# FTDI_breakout-v1_0.net
KiCad netlist of a schematic drawn in EAGLE
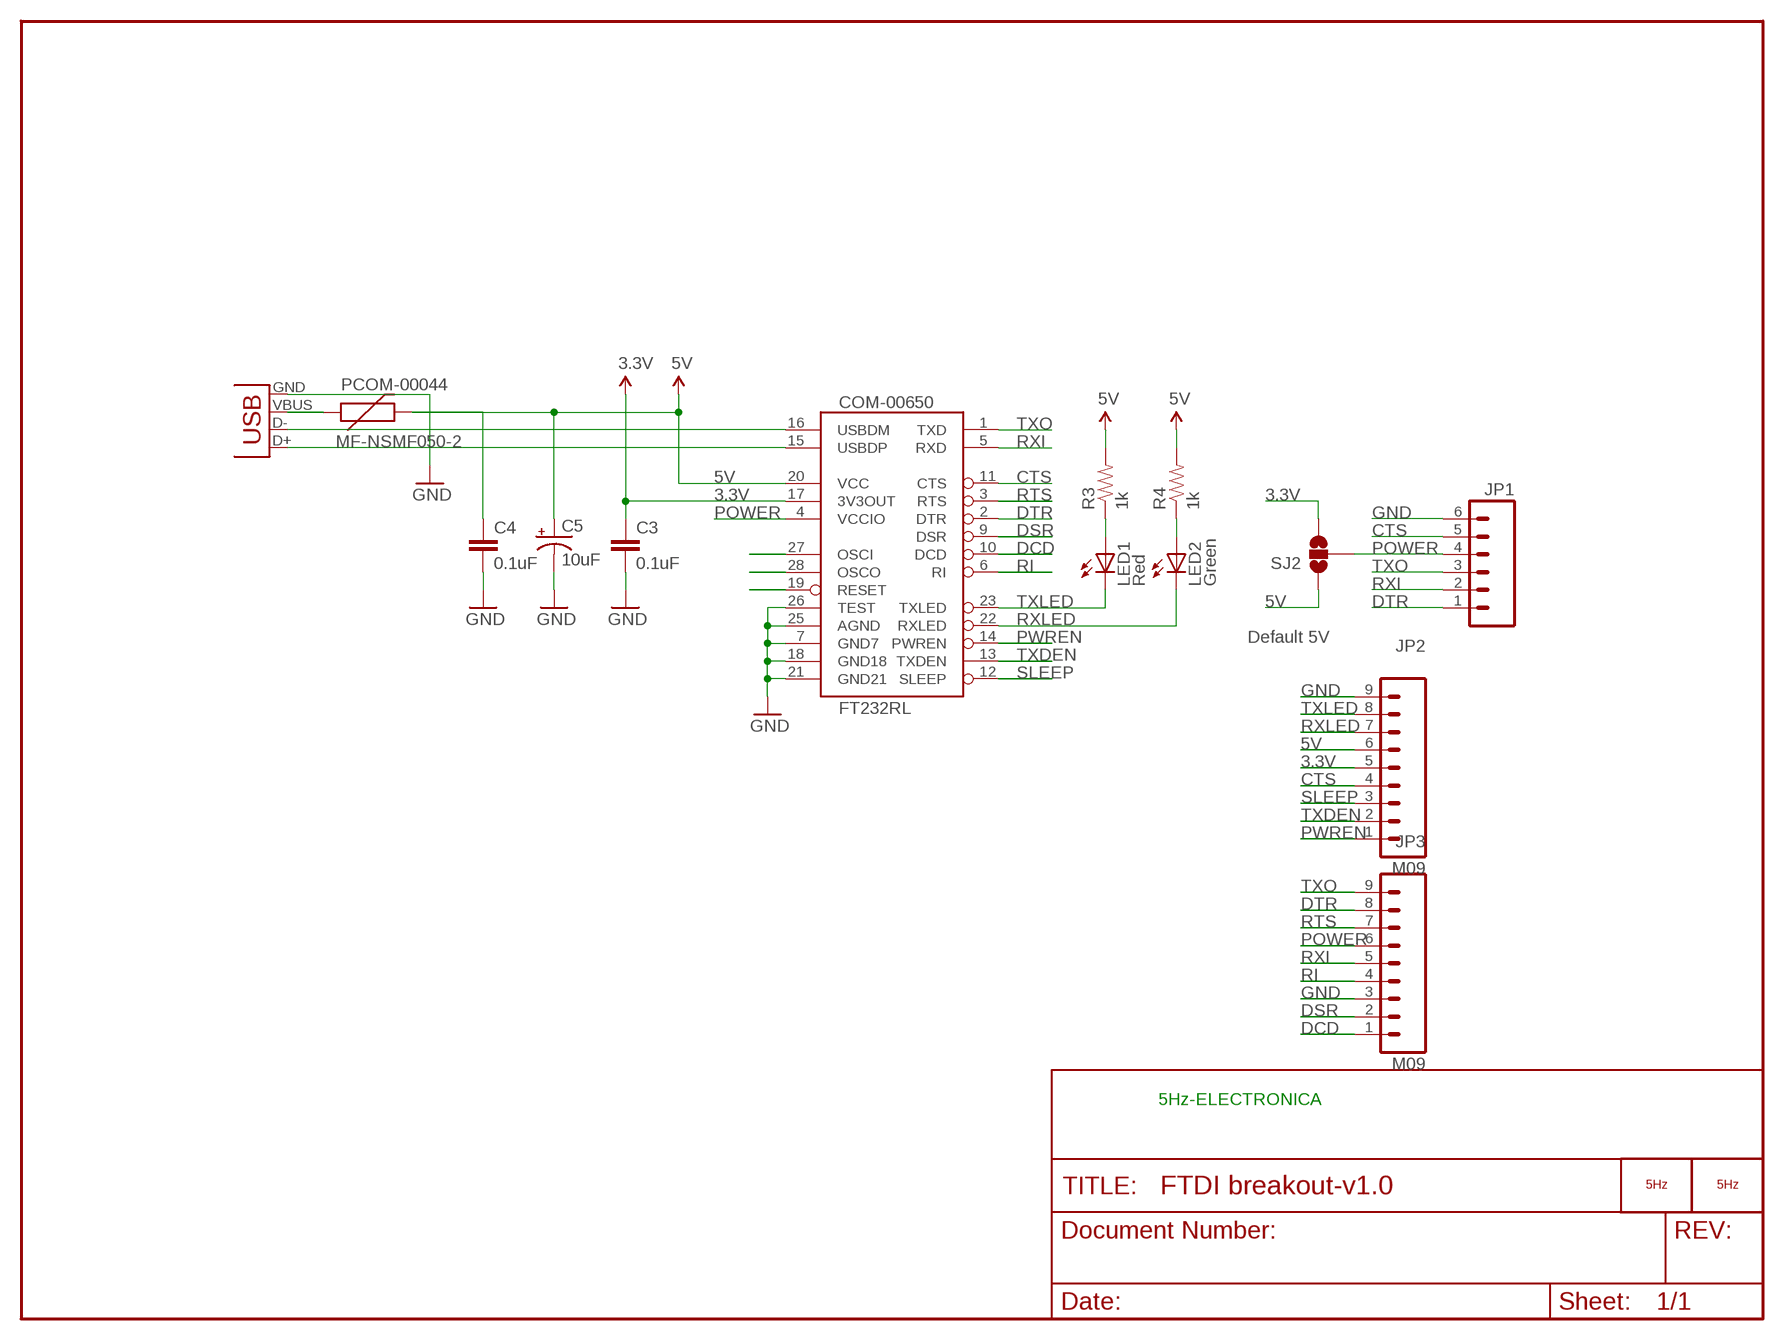
[diagram p0: schematic, sheet 1]

(export (version "E")
  (design (tool "Eeschema 10.0.6"))
  (components
    (comp (ref "C3")
      (value "0.1uF")
      (footprint "eagle-import:0603-CAP")
      (libsource (lib "eagle-import") (part "CAP0603-CAP"))
    )
    (comp (ref "C4")
      (value "0.1uF")
      (footprint "eagle-import:0603-CAP")
      (libsource (lib "eagle-import") (part "CAP0603-CAP"))
    )
    (comp (ref "C5")
      (value "10uF")
      (footprint "eagle-import:EIA3216")
      (libsource (lib "eagle-import") (part "CAP_POL1206"))
    )
    (comp (ref "COM-00650")
      (value "FT232RL")
      (footprint "eagle-import:SSOP28DB")
      (libsource (lib "eagle-import") (part "FT232RLSSOP"))
    )
    (comp (ref "JP1")
      (value "M06SIP")
      (footprint "eagle-import:1X06")
      (libsource (lib "eagle-import") (part "M06SIP"))
    )
    (comp (ref "JP2")
      (value "M09")
      (footprint "eagle-import:1X09")
      (libsource (lib "eagle-import") (part "M09"))
    )
    (comp (ref "JP3")
      (value "M09")
      (footprint "eagle-import:1X09")
      (libsource (lib "eagle-import") (part "M09"))
    )
    (comp (ref "LED1")
      (value "Red")
      (footprint "eagle-import:LED-0603")
      (libsource (lib "eagle-import") (part "LED0603"))
    )
    (comp (ref "LED2")
      (value "Green")
      (footprint "eagle-import:LED-0603")
      (libsource (lib "eagle-import") (part "LED0603"))
    )
    (comp (ref "LOGO1")
      (value "LOGO_5HZ_H_5MM")
      (footprint "eagle-import:5HZ_LOGO_H_5MM")
      (libsource (lib "eagle-import") (part "LOGO_5HZ_H_5MM"))
    )
    (comp (ref "LOGO2")
      (value "LOGO_5HZ_H_15MM")
      (footprint "eagle-import:5HZ_LOGO_H_15MM")
      (libsource (lib "eagle-import") (part "LOGO_5HZ_H_15MM"))
    )
    (comp (ref "PCOM-00044")
      (value "MF-NSMF050-2")
      (footprint "eagle-import:PTC-1206")
      (libsource (lib "eagle-import") (part "PTCSMD"))
    )
    (comp (ref "PRT-00587")
      (value "897-43-005-00-100001")
      (footprint "eagle-import:USB-MINIB")
      (libsource (lib "eagle-import") (part "USBSMD"))
    )
    (comp (ref "R3")
      (value "1k")
      (footprint "eagle-import:0603-RES")
      (libsource (lib "eagle-import") (part "RESISTOR0603-RES"))
    )
    (comp (ref "R4")
      (value "1k")
      (footprint "eagle-import:0603-RES")
      (libsource (lib "eagle-import") (part "RESISTOR0603-RES"))
    )
    (comp (ref "SJ2")
      (value "SOLDERJUMPER_2WAYS")
      (footprint "eagle-import:SJ_3")
      (libsource (lib "eagle-import") (part "SOLDERJUMPER_2WAYS"))
    )
  )
  (nets
    (net (code "1") (name "/CTS") (class "Default")
      (node (ref "COM-00650") (pin "11") (pinfunction "CTS_11") (pintype "input"))
      (node (ref "JP1") (pin "5") (pinfunction "5_5") (pintype "passive"))
      (node (ref "JP2") (pin "4") (pinfunction "4_4") (pintype "passive"))
    )
    (net (code "2") (name "/DCD") (class "Default")
      (node (ref "COM-00650") (pin "10") (pinfunction "DCD_10") (pintype "input"))
      (node (ref "JP3") (pin "1") (pinfunction "1_1") (pintype "passive"))
    )
    (net (code "3") (name "/DSR") (class "Default")
      (node (ref "COM-00650") (pin "9") (pinfunction "DSR_9") (pintype "input"))
      (node (ref "JP3") (pin "2") (pinfunction "2_2") (pintype "passive"))
    )
    (net (code "4") (name "/DTR") (class "Default")
      (node (ref "COM-00650") (pin "2") (pinfunction "DTR_2") (pintype "output"))
      (node (ref "JP1") (pin "1") (pinfunction "1_1") (pintype "passive"))
      (node (ref "JP3") (pin "8") (pinfunction "8_8") (pintype "passive"))
    )
    (net (code "5") (name "/POWER") (class "Default")
      (node (ref "COM-00650") (pin "4") (pinfunction "VCCIO_4") (pintype "power_in"))
      (node (ref "JP1") (pin "4") (pinfunction "4_4") (pintype "passive"))
      (node (ref "JP3") (pin "6") (pinfunction "6_6") (pintype "passive"))
      (node (ref "SJ2") (pin "2") (pinfunction "2_2") (pintype "passive"))
    )
    (net (code "6") (name "/PWREN") (class "Default")
      (node (ref "COM-00650") (pin "14") (pinfunction "PWREN_14") (pintype "input"))
      (node (ref "JP2") (pin "1") (pinfunction "1_1") (pintype "passive"))
    )
    (net (code "7") (name "/RI") (class "Default")
      (node (ref "COM-00650") (pin "6") (pinfunction "RI_6") (pintype "input"))
      (node (ref "JP3") (pin "4") (pinfunction "4_4") (pintype "passive"))
    )
    (net (code "8") (name "/RTS") (class "Default")
      (node (ref "COM-00650") (pin "3") (pinfunction "RTS_3") (pintype "output"))
      (node (ref "JP3") (pin "7") (pinfunction "7_7") (pintype "passive"))
    )
    (net (code "9") (name "/RXI") (class "Default")
      (node (ref "COM-00650") (pin "5") (pinfunction "RXD_5") (pintype "input"))
      (node (ref "JP1") (pin "2") (pinfunction "2_2") (pintype "passive"))
      (node (ref "JP3") (pin "5") (pinfunction "5_5") (pintype "passive"))
    )
    (net (code "10") (name "/RXLED") (class "Default")
      (node (ref "COM-00650") (pin "22") (pinfunction "RXLED_22") (pintype "input"))
      (node (ref "JP2") (pin "7") (pinfunction "7_7") (pintype "passive"))
      (node (ref "LED2") (pin "C") (pinfunction "C_C") (pintype "passive"))
    )
    (net (code "11") (name "/SLEEP") (class "Default")
      (node (ref "COM-00650") (pin "12") (pinfunction "SLEEP_12") (pintype "input"))
      (node (ref "JP2") (pin "3") (pinfunction "3_3") (pintype "passive"))
    )
    (net (code "12") (name "/TXDEN") (class "Default")
      (node (ref "COM-00650") (pin "13") (pinfunction "TXDEN_13") (pintype "input"))
      (node (ref "JP2") (pin "2") (pinfunction "2_2") (pintype "passive"))
    )
    (net (code "13") (name "/TXLED") (class "Default")
      (node (ref "COM-00650") (pin "23") (pinfunction "TXLED_23") (pintype "input"))
      (node (ref "JP2") (pin "8") (pinfunction "8_8") (pintype "passive"))
      (node (ref "LED1") (pin "C") (pinfunction "C_C") (pintype "passive"))
    )
    (net (code "14") (name "/TXO") (class "Default")
      (node (ref "COM-00650") (pin "1") (pinfunction "TXD_1") (pintype "output"))
      (node (ref "JP1") (pin "3") (pinfunction "3_3") (pintype "passive"))
      (node (ref "JP3") (pin "9") (pinfunction "9_9") (pintype "passive"))
    )
    (net (code "15") (name "3.3V") (class "Default")
      (node (ref "C3") (pin "1") (pinfunction "1_1") (pintype "passive"))
      (node (ref "COM-00650") (pin "17") (pinfunction "3V3OUT_17") (pintype "output"))
      (node (ref "JP2") (pin "5") (pinfunction "5_5") (pintype "passive"))
      (node (ref "SJ2") (pin "3") (pinfunction "3_3") (pintype "passive"))
    )
    (net (code "16") (name "5V") (class "Default")
      (node (ref "C4") (pin "1") (pinfunction "1_1") (pintype "passive"))
      (node (ref "C5") (pin "A") (pinfunction "+_A") (pintype "passive"))
      (node (ref "COM-00650") (pin "20") (pinfunction "VCC_20") (pintype "power_in"))
      (node (ref "JP2") (pin "6") (pinfunction "6_6") (pintype "passive"))
      (node (ref "PCOM-00044") (pin "2") (pinfunction "2_2") (pintype "bidirectional"))
      (node (ref "R3") (pin "2") (pinfunction "2_2") (pintype "passive"))
      (node (ref "R4") (pin "2") (pinfunction "2_2") (pintype "passive"))
      (node (ref "SJ2") (pin "1") (pinfunction "1_1") (pintype "passive"))
    )
    (net (code "17") (name "GND") (class "Default")
      (node (ref "C3") (pin "2") (pinfunction "2_2") (pintype "passive"))
      (node (ref "C4") (pin "2") (pinfunction "2_2") (pintype "passive"))
      (node (ref "C5") (pin "C") (pinfunction "-_C") (pintype "passive"))
      (node (ref "COM-00650") (pin "18") (pinfunction "GND18_18") (pintype "power_in"))
      (node (ref "COM-00650") (pin "21") (pinfunction "GND21_21") (pintype "power_in"))
      (node (ref "COM-00650") (pin "25") (pinfunction "AGND_25") (pintype "power_in"))
      (node (ref "COM-00650") (pin "26") (pinfunction "TEST_26") (pintype "input"))
      (node (ref "COM-00650") (pin "7") (pinfunction "GND7_7") (pintype "power_in"))
      (node (ref "JP1") (pin "6") (pinfunction "6_6") (pintype "passive"))
      (node (ref "JP2") (pin "9") (pinfunction "9_9") (pintype "passive"))
      (node (ref "JP3") (pin "3") (pinfunction "3_3") (pintype "passive"))
      (node (ref "PRT-00587") (pin "GND") (pinfunction "GND_GND") (pintype "bidirectional"))
    )
    (net (code "18") (name "Net-(COM-00650-USBDM)") (class "Default")
      (node (ref "COM-00650") (pin "16") (pinfunction "USBDM_16") (pintype "bidirectional"))
      (node (ref "PRT-00587") (pin "D-") (pinfunction "D-_D-") (pintype "bidirectional"))
    )
    (net (code "19") (name "Net-(COM-00650-USBDP)") (class "Default")
      (node (ref "COM-00650") (pin "15") (pinfunction "USBDP_15") (pintype "bidirectional"))
      (node (ref "PRT-00587") (pin "D+") (pinfunction "D+_D+") (pintype "bidirectional"))
    )
    (net (code "20") (name "Net-(LED1-PadA)") (class "Default")
      (node (ref "LED1") (pin "A") (pinfunction "A_A") (pintype "passive"))
      (node (ref "R3") (pin "1") (pinfunction "1_1") (pintype "passive"))
    )
    (net (code "21") (name "Net-(LED2-PadA)") (class "Default")
      (node (ref "LED2") (pin "A") (pinfunction "A_A") (pintype "passive"))
      (node (ref "R4") (pin "1") (pinfunction "1_1") (pintype "passive"))
    )
    (net (code "22") (name "Net-(PCOM-00044-Pad1)") (class "Default")
      (node (ref "PCOM-00044") (pin "1") (pinfunction "1_1") (pintype "bidirectional"))
      (node (ref "PRT-00587") (pin "VBUS") (pinfunction "VBUS_VBUS") (pintype "bidirectional"))
    )
    (net (code "23") (name "unconnected-(COM-00650-OSCI-Pad27)") (class "Default")
      (node (ref "COM-00650") (pin "27") (pinfunction "OSCI_27") (pintype "input"))
    )
    (net (code "24") (name "unconnected-(COM-00650-OSCO-Pad28)") (class "Default")
      (node (ref "COM-00650") (pin "28") (pinfunction "OSCO_28") (pintype "output"))
    )
    (net (code "25") (name "unconnected-(COM-00650-RESET-Pad19)") (class "Default")
      (node (ref "COM-00650") (pin "19") (pinfunction "RESET_19") (pintype "input"))
    )
  )
)
